# flight_controller.net
KiCad netlist of a schematic drawn in EasyEDA Pro
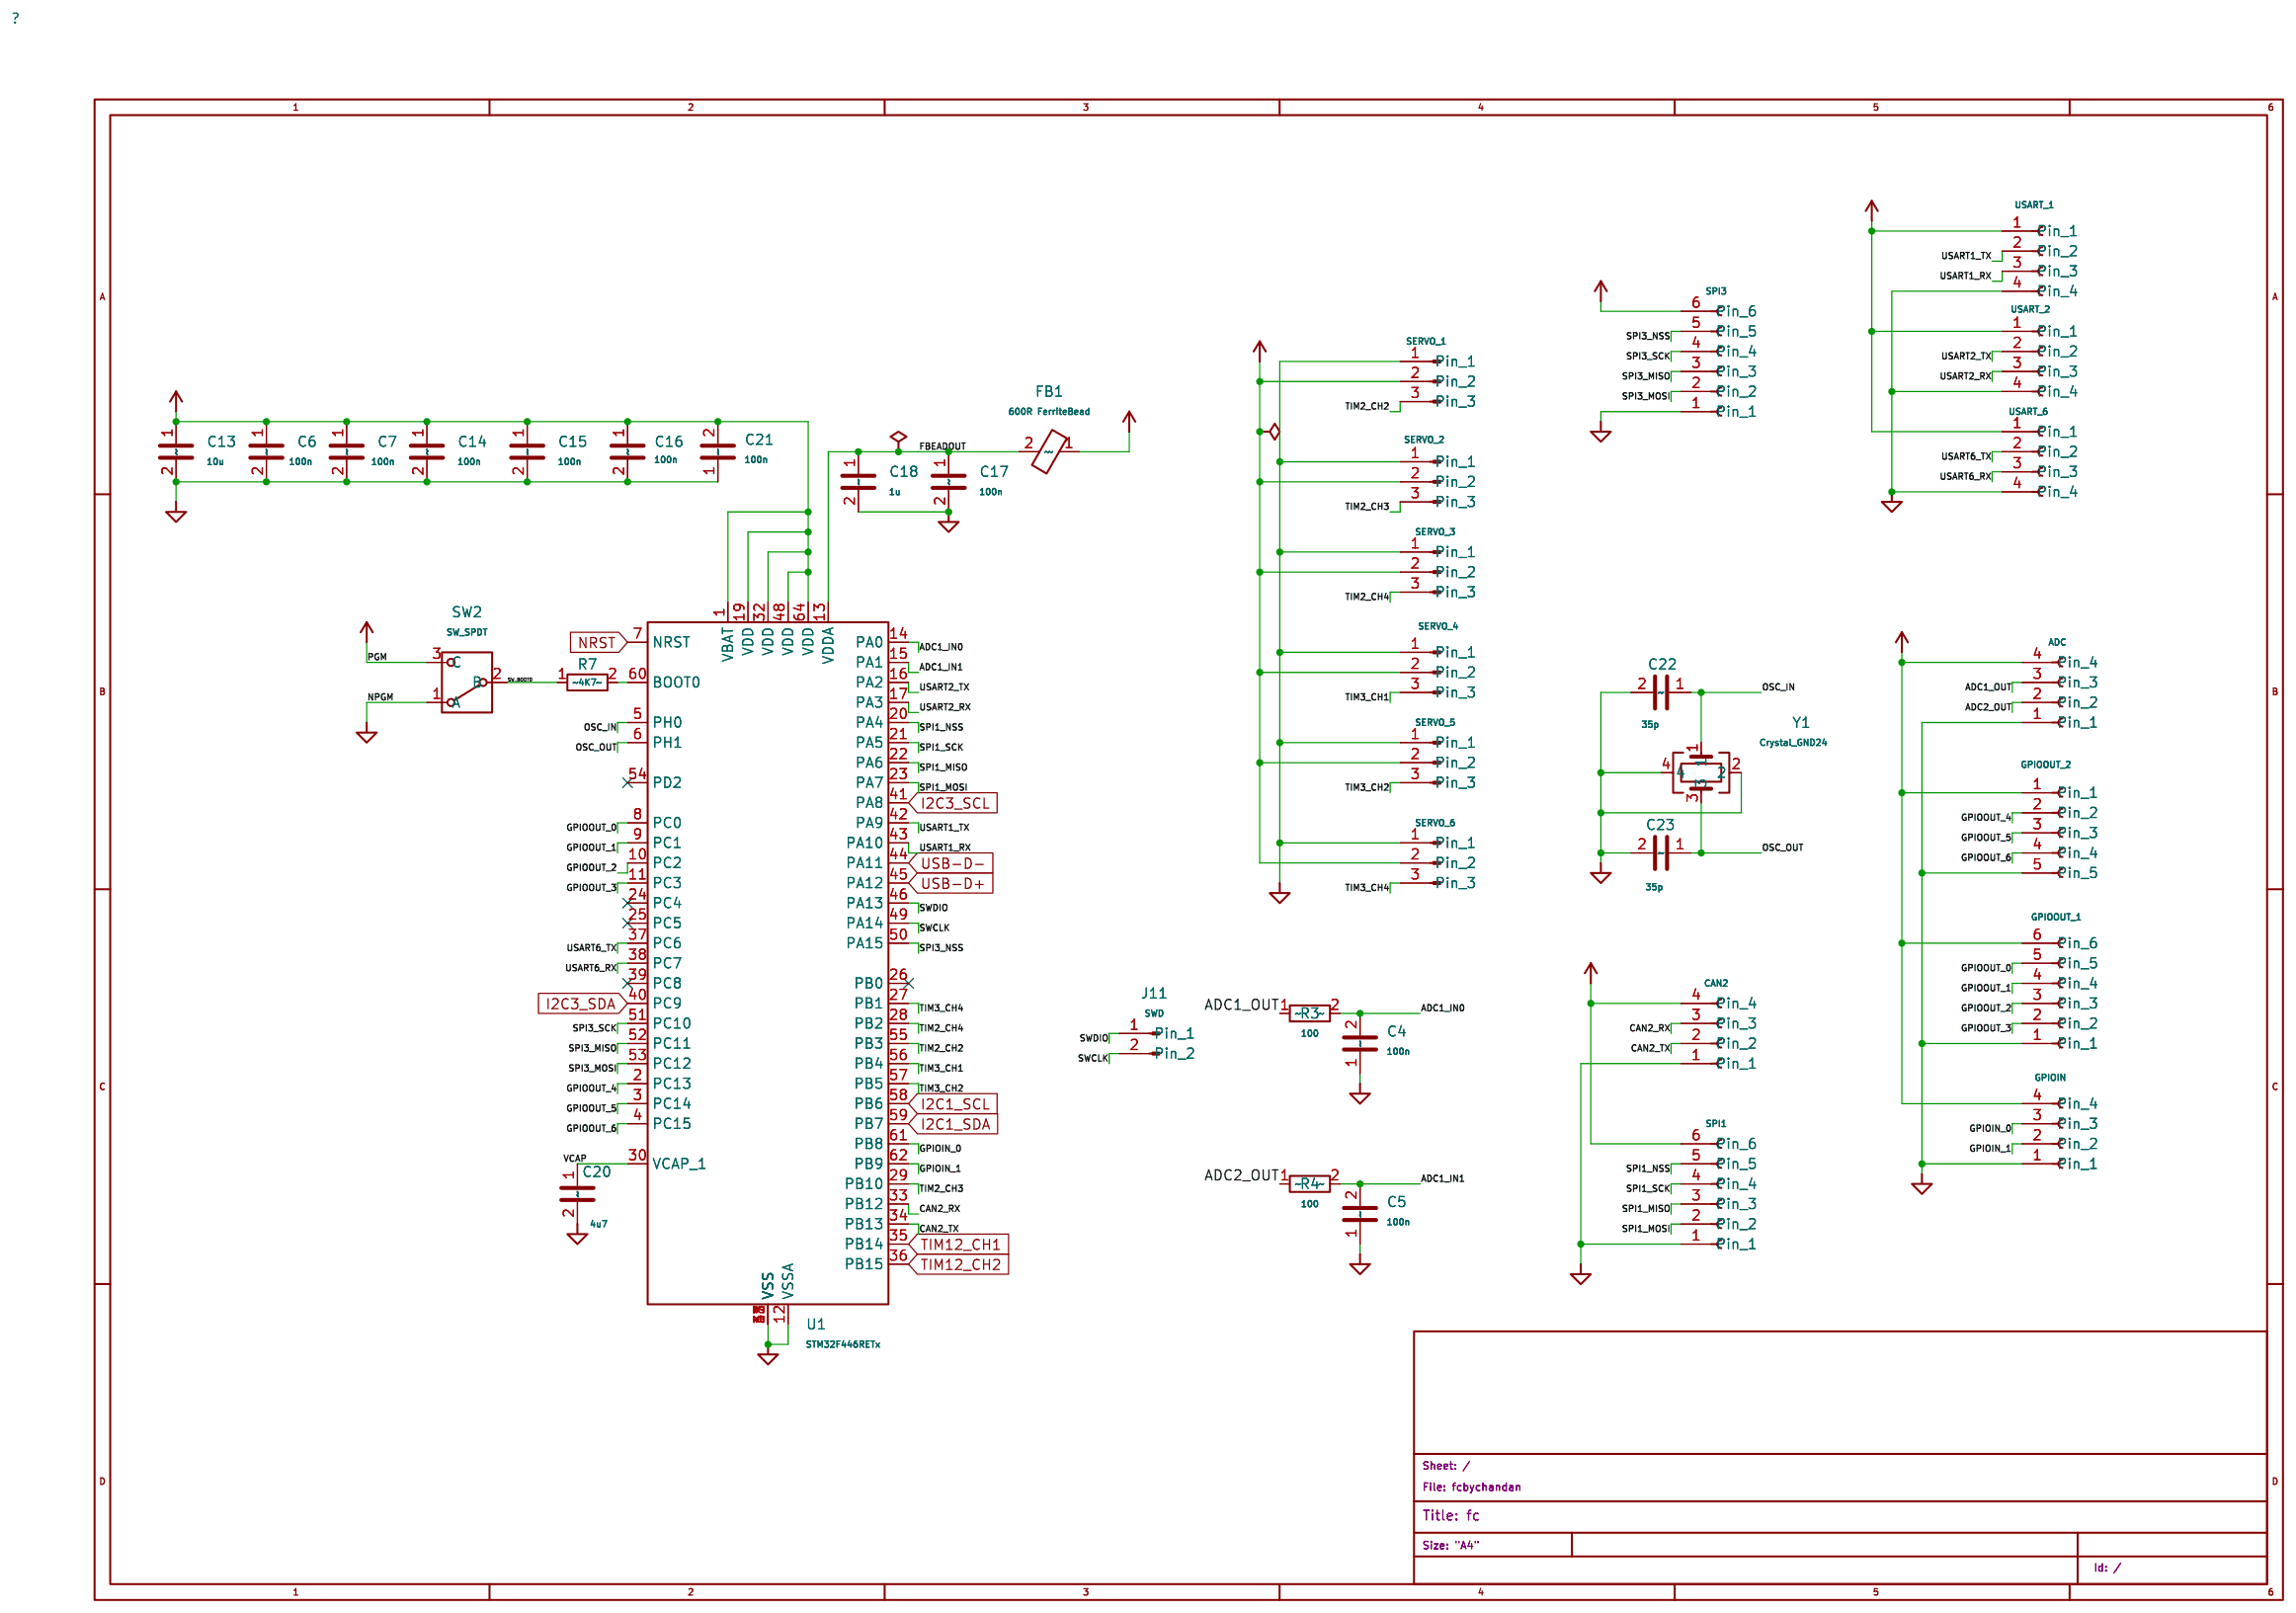
[diagram p0: schematic sheet]

(export (version "E")
  (design (tool "Eeschema 10.0.6"))
  (components
    (comp (ref "C4")
      (value "100n")
      (description "Unpolarized capacitor")
      (libsource (lib "easyedapro") (part "Device_C"))
    )
    (comp (ref "C5")
      (value "100n")
      (description "Unpolarized capacitor")
      (libsource (lib "easyedapro") (part "Device_C"))
    )
    (comp (ref "C6")
      (value "100n")
      (description "Unpolarized capacitor")
      (libsource (lib "easyedapro") (part "Device_C"))
    )
    (comp (ref "C7")
      (value "100n")
      (description "Unpolarized capacitor")
      (libsource (lib "easyedapro") (part "Device_C"))
    )
    (comp (ref "C13")
      (value "10u")
      (description "Unpolarized capacitor")
      (libsource (lib "easyedapro") (part "Device_C"))
    )
    (comp (ref "C14")
      (value "100n")
      (description "Unpolarized capacitor")
      (libsource (lib "easyedapro") (part "Device_C"))
    )
    (comp (ref "C15")
      (value "100n")
      (description "Unpolarized capacitor")
      (libsource (lib "easyedapro") (part "Device_C"))
    )
    (comp (ref "C16")
      (value "100n")
      (description "Unpolarized capacitor")
      (libsource (lib "easyedapro") (part "Device_C"))
    )
    (comp (ref "C17")
      (value "100n")
      (description "Unpolarized capacitor")
      (libsource (lib "easyedapro") (part "Device_C"))
    )
    (comp (ref "C18")
      (value "1u")
      (description "Unpolarized capacitor")
      (libsource (lib "easyedapro") (part "Device_C"))
    )
    (comp (ref "C20")
      (value "4u7")
      (description "Unpolarized capacitor")
      (libsource (lib "easyedapro") (part "Device_C"))
    )
    (comp (ref "C21")
      (value "100n")
      (description "Unpolarized capacitor")
      (libsource (lib "easyedapro") (part "Device_C"))
    )
    (comp (ref "C22")
      (value "35p")
      (description "Unpolarized capacitor")
      (libsource (lib "easyedapro") (part "Device_C"))
    )
    (comp (ref "C23")
      (value "35p")
      (description "Unpolarized capacitor")
      (libsource (lib "easyedapro") (part "Device_C"))
    )
    (comp (ref "FB1")
      (value "600R FerriteBead")
      (description "Ferrite bead")
      (libsource (lib "easyedapro") (part "Device_FerriteBead"))
    )
    (comp (ref "J1")
      (value "SPI3")
      (description "Generic connector, single row, 01x06, script generated")
      (libsource (lib "easyedapro") (part "Connector_Conn_01x06_Socket"))
    )
    (comp (ref "J2")
      (value "GPIOOUT_1")
      (description "Generic connector, single row, 01x06, script generated")
      (libsource (lib "easyedapro") (part "Connector_Conn_01x06_Socket"))
    )
    (comp (ref "J3")
      (value "USART_1")
      (description "Generic connector, single row, 01x04, script generated")
      (libsource (lib "easyedapro") (part "Connector_Conn_01x04_Socket"))
    )
    (comp (ref "J4")
      (value "GPIOIN")
      (description "Generic connector, single row, 01x04, script generated")
      (libsource (lib "easyedapro") (part "Connector_Conn_01x04_Socket"))
    )
    (comp (ref "J5")
      (value "ADC")
      (description "Generic connector, single row, 01x04, script generated")
      (libsource (lib "easyedapro") (part "Connector_Conn_01x04_Socket"))
    )
    (comp (ref "J6")
      (value "USART_2")
      (description "Generic connector, single row, 01x04, script generated")
      (libsource (lib "easyedapro") (part "Connector_Conn_01x04_Socket"))
    )
    (comp (ref "J7")
      (value "USART_6")
      (description "Generic connector, single row, 01x04, script generated")
      (libsource (lib "easyedapro") (part "Connector_Conn_01x04_Socket"))
    )
    (comp (ref "J8")
      (value "SERVO_1")
      (description "Generic connector, single row, 01x03, script generated")
      (libsource (lib "easyedapro") (part "Connector_Conn_01x03_Pin"))
    )
    (comp (ref "J9")
      (value "SERVO_2")
      (description "Generic connector, single row, 01x03, script generated")
      (libsource (lib "easyedapro") (part "Connector_Conn_01x03_Pin"))
    )
    (comp (ref "J10")
      (value "GPIOOUT_2")
      (description "Generic connector, single row, 01x05, script generated")
      (libsource (lib "easyedapro") (part "Connector_Conn_01x05_Socket"))
    )
    (comp (ref "J11")
      (value "SWD")
      (description "Generic connector, single row, 01x02, script generated")
      (libsource (lib "easyedapro") (part "Connector_Conn_01x02_Pin"))
    )
    (comp (ref "J12")
      (value "SERVO_5")
      (description "Generic connector, single row, 01x03, script generated")
      (libsource (lib "easyedapro") (part "Connector_Conn_01x03_Pin"))
    )
    (comp (ref "J13")
      (value "SERVO_4")
      (description "Generic connector, single row, 01x03, script generated")
      (libsource (lib "easyedapro") (part "Connector_Conn_01x03_Pin"))
    )
    (comp (ref "J14")
      (value "SERVO_6")
      (description "Generic connector, single row, 01x03, script generated")
      (libsource (lib "easyedapro") (part "Connector_Conn_01x03_Pin"))
    )
    (comp (ref "J15")
      (value "SERVO_3")
      (description "Generic connector, single row, 01x03, script generated")
      (libsource (lib "easyedapro") (part "Connector_Conn_01x03_Pin"))
    )
    (comp (ref "J17")
      (value "SPI1")
      (description "Generic connector, single row, 01x06, script generated")
      (libsource (lib "easyedapro") (part "Connector_Conn_01x06_Socket"))
    )
    (comp (ref "J18")
      (value "CAN2")
      (description "Generic connector, single row, 01x04, script generated")
      (libsource (lib "easyedapro") (part "Connector_Conn_01x04_Socket"))
    )
    (comp (ref "R3") (value "100") (description "Resistor") (libsource (lib "easyedapro") (part "Device_R")))
    (comp (ref "R4") (value "100") (description "Resistor") (libsource (lib "easyedapro") (part "Device_R")))
    (comp (ref "R7") (value "4K7") (description "Resistor") (libsource (lib "easyedapro") (part "Device_R")))
    (comp (ref "SW2")
      (value "SW_SPDT")
      (description "Switch, single pole double throw")
      (libsource (lib "easyedapro") (part "Switch_SW_SPDT"))
    )
    (comp (ref "U1")
      (value "STM32F446RETx")
      (description "STMicroelectronics Arm Cortex-M4 MCU, 512KB flash, 128KB RAM, 180 MHz, 1.8-3.6V, 50 GPIO, LQFP64")
      (libsource (lib "easyedapro") (part "MCU_ST_STM32F4_STM32F446RETx"))
    )
    (comp (ref "Y1")
      (value "Crystal_GND24")
      (description "Four pin crystal, GND on pins 2 and 4")
      (libsource (lib "easyedapro") (part "Device_Crystal_GND24"))
    )
  )
  (nets
    (net (code "1") (name "/ADC1_IN0") (class "Default")
      (node (ref "C4") (pin "2") (pinfunction "~_2") (pintype "unspecified"))
      (node (ref "R3") (pin "2") (pinfunction "~_2") (pintype "unspecified"))
      (node (ref "U1") (pin "14") (pinfunction "PA0_14") (pintype "bidirectional"))
    )
    (net (code "2") (name "/ADC1_IN1") (class "Default")
      (node (ref "C5") (pin "2") (pinfunction "~_2") (pintype "unspecified"))
      (node (ref "R4") (pin "2") (pinfunction "~_2") (pintype "unspecified"))
      (node (ref "U1") (pin "15") (pinfunction "PA1_15") (pintype "bidirectional"))
    )
    (net (code "3") (name "/ADC1_OUT") (class "Default")
      (node (ref "J5") (pin "3") (pinfunction "Pin_3_3") (pintype "unspecified"))
      (node (ref "R3") (pin "1") (pinfunction "~_1") (pintype "unspecified"))
    )
    (net (code "4") (name "/ADC2_OUT") (class "Default")
      (node (ref "J5") (pin "2") (pinfunction "Pin_2_2") (pintype "unspecified"))
      (node (ref "R4") (pin "1") (pinfunction "~_1") (pintype "unspecified"))
    )
    (net (code "5") (name "/CAN2_RX") (class "Default")
      (node (ref "J18") (pin "3") (pinfunction "Pin_3_3") (pintype "unspecified"))
      (node (ref "U1") (pin "33") (pinfunction "PB12_33") (pintype "bidirectional"))
    )
    (net (code "6") (name "/CAN2_TX") (class "Default")
      (node (ref "J18") (pin "2") (pinfunction "Pin_2_2") (pintype "unspecified"))
      (node (ref "U1") (pin "34") (pinfunction "PB13_34") (pintype "bidirectional"))
    )
    (net (code "7") (name "/GPIOIN_0") (class "Default")
      (node (ref "J4") (pin "3") (pinfunction "Pin_3_3") (pintype "unspecified"))
      (node (ref "U1") (pin "61") (pinfunction "PB8_61") (pintype "bidirectional"))
    )
    (net (code "8") (name "/GPIOIN_1") (class "Default")
      (node (ref "J4") (pin "2") (pinfunction "Pin_2_2") (pintype "unspecified"))
      (node (ref "U1") (pin "62") (pinfunction "PB9_62") (pintype "bidirectional"))
    )
    (net (code "9") (name "/GPIOOUT_0") (class "Default")
      (node (ref "J2") (pin "5") (pinfunction "Pin_5_5") (pintype "unspecified"))
      (node (ref "U1") (pin "8") (pinfunction "PC0_8") (pintype "bidirectional"))
    )
    (net (code "10") (name "/GPIOOUT_1") (class "Default")
      (node (ref "J2") (pin "4") (pinfunction "Pin_4_4") (pintype "unspecified"))
      (node (ref "U1") (pin "9") (pinfunction "PC1_9") (pintype "bidirectional"))
    )
    (net (code "11") (name "/GPIOOUT_2") (class "Default")
      (node (ref "J2") (pin "3") (pinfunction "Pin_3_3") (pintype "unspecified"))
      (node (ref "U1") (pin "10") (pinfunction "PC2_10") (pintype "bidirectional"))
    )
    (net (code "12") (name "/GPIOOUT_3") (class "Default")
      (node (ref "J2") (pin "2") (pinfunction "Pin_2_2") (pintype "unspecified"))
      (node (ref "U1") (pin "11") (pinfunction "PC3_11") (pintype "bidirectional"))
    )
    (net (code "13") (name "/GPIOOUT_4") (class "Default")
      (node (ref "J10") (pin "2") (pinfunction "Pin_2_2") (pintype "unspecified"))
      (node (ref "U1") (pin "2") (pinfunction "PC13_2") (pintype "bidirectional"))
    )
    (net (code "14") (name "/GPIOOUT_5") (class "Default")
      (node (ref "J10") (pin "3") (pinfunction "Pin_3_3") (pintype "unspecified"))
      (node (ref "U1") (pin "3") (pinfunction "PC14_3") (pintype "bidirectional"))
    )
    (net (code "15") (name "/GPIOOUT_6") (class "Default")
      (node (ref "J10") (pin "4") (pinfunction "Pin_4_4") (pintype "unspecified"))
      (node (ref "U1") (pin "4") (pinfunction "PC15_4") (pintype "bidirectional"))
    )
    (net (code "16") (name "/OSC_IN") (class "Default")
      (node (ref "C22") (pin "1") (pinfunction "~_1") (pintype "unspecified"))
      (node (ref "U1") (pin "5") (pinfunction "PH0_5") (pintype "bidirectional"))
      (node (ref "Y1") (pin "1") (pinfunction "1_1") (pintype "unspecified"))
    )
    (net (code "17") (name "/OSC_OUT") (class "Default")
      (node (ref "C23") (pin "1") (pinfunction "~_1") (pintype "unspecified"))
      (node (ref "U1") (pin "6") (pinfunction "PH1_6") (pintype "bidirectional"))
      (node (ref "Y1") (pin "3") (pinfunction "3_3") (pintype "unspecified"))
    )
    (net (code "18") (name "/SPI1_MISO") (class "Default")
      (node (ref "J17") (pin "3") (pinfunction "Pin_3_3") (pintype "unspecified"))
      (node (ref "U1") (pin "22") (pinfunction "PA6_22") (pintype "bidirectional"))
    )
    (net (code "19") (name "/SPI1_MOSI") (class "Default")
      (node (ref "J17") (pin "2") (pinfunction "Pin_2_2") (pintype "unspecified"))
      (node (ref "U1") (pin "23") (pinfunction "PA7_23") (pintype "bidirectional"))
    )
    (net (code "20") (name "/SPI1_NSS") (class "Default")
      (node (ref "J17") (pin "5") (pinfunction "Pin_5_5") (pintype "unspecified"))
      (node (ref "U1") (pin "20") (pinfunction "PA4_20") (pintype "bidirectional"))
    )
    (net (code "21") (name "/SPI1_SCK") (class "Default")
      (node (ref "J17") (pin "4") (pinfunction "Pin_4_4") (pintype "unspecified"))
      (node (ref "U1") (pin "21") (pinfunction "PA5_21") (pintype "bidirectional"))
    )
    (net (code "22") (name "/SPI3_MISO") (class "Default")
      (node (ref "J1") (pin "3") (pinfunction "Pin_3_3") (pintype "unspecified"))
      (node (ref "U1") (pin "52") (pinfunction "PC11_52") (pintype "bidirectional"))
    )
    (net (code "23") (name "/SPI3_MOSI") (class "Default")
      (node (ref "J1") (pin "2") (pinfunction "Pin_2_2") (pintype "unspecified"))
      (node (ref "U1") (pin "53") (pinfunction "PC12_53") (pintype "bidirectional"))
    )
    (net (code "24") (name "/SPI3_NSS") (class "Default")
      (node (ref "J1") (pin "5") (pinfunction "Pin_5_5") (pintype "unspecified"))
      (node (ref "U1") (pin "50") (pinfunction "PA15_50") (pintype "bidirectional"))
    )
    (net (code "25") (name "/SPI3_SCK") (class "Default")
      (node (ref "J1") (pin "4") (pinfunction "Pin_4_4") (pintype "unspecified"))
      (node (ref "U1") (pin "51") (pinfunction "PC10_51") (pintype "bidirectional"))
    )
    (net (code "26") (name "/SWCLK") (class "Default")
      (node (ref "J11") (pin "2") (pinfunction "Pin_2_2") (pintype "unspecified"))
      (node (ref "U1") (pin "49") (pinfunction "PA14_49") (pintype "bidirectional"))
    )
    (net (code "27") (name "/SWDIO") (class "Default")
      (node (ref "J11") (pin "1") (pinfunction "Pin_1_1") (pintype "unspecified"))
      (node (ref "U1") (pin "46") (pinfunction "PA13_46") (pintype "bidirectional"))
    )
    (net (code "28") (name "/SW_BOOT0") (class "Default")
      (node (ref "R7") (pin "1") (pinfunction "~_1") (pintype "unspecified"))
      (node (ref "SW2") (pin "2") (pinfunction "B_2") (pintype "unspecified"))
    )
    (net (code "29") (name "/TIM2_CH2") (class "Default")
      (node (ref "J8") (pin "3") (pinfunction "Pin_3_3") (pintype "unspecified"))
      (node (ref "U1") (pin "55") (pinfunction "PB3_55") (pintype "bidirectional"))
    )
    (net (code "30") (name "/TIM2_CH3") (class "Default")
      (node (ref "J9") (pin "3") (pinfunction "Pin_3_3") (pintype "unspecified"))
      (node (ref "U1") (pin "29") (pinfunction "PB10_29") (pintype "bidirectional"))
    )
    (net (code "31") (name "/TIM2_CH4") (class "Default")
      (node (ref "J15") (pin "3") (pinfunction "Pin_3_3") (pintype "unspecified"))
      (node (ref "U1") (pin "28") (pinfunction "PB2_28") (pintype "bidirectional"))
    )
    (net (code "32") (name "/TIM3_CH1") (class "Default")
      (node (ref "J13") (pin "3") (pinfunction "Pin_3_3") (pintype "unspecified"))
      (node (ref "U1") (pin "56") (pinfunction "PB4_56") (pintype "bidirectional"))
    )
    (net (code "33") (name "/TIM3_CH2") (class "Default")
      (node (ref "J12") (pin "3") (pinfunction "Pin_3_3") (pintype "unspecified"))
      (node (ref "U1") (pin "57") (pinfunction "PB5_57") (pintype "bidirectional"))
    )
    (net (code "34") (name "/TIM3_CH4") (class "Default")
      (node (ref "J14") (pin "3") (pinfunction "Pin_3_3") (pintype "unspecified"))
      (node (ref "U1") (pin "27") (pinfunction "PB1_27") (pintype "bidirectional"))
    )
    (net (code "35") (name "/USART1_RX") (class "Default")
      (node (ref "J3") (pin "3") (pinfunction "Pin_3_3") (pintype "unspecified"))
      (node (ref "U1") (pin "43") (pinfunction "PA10_43") (pintype "bidirectional"))
    )
    (net (code "36") (name "/USART1_TX") (class "Default")
      (node (ref "J3") (pin "2") (pinfunction "Pin_2_2") (pintype "unspecified"))
      (node (ref "U1") (pin "42") (pinfunction "PA9_42") (pintype "bidirectional"))
    )
    (net (code "37") (name "/USART2_RX") (class "Default")
      (node (ref "J6") (pin "3") (pinfunction "Pin_3_3") (pintype "unspecified"))
      (node (ref "U1") (pin "17") (pinfunction "PA3_17") (pintype "bidirectional"))
    )
    (net (code "38") (name "/USART2_TX") (class "Default")
      (node (ref "J6") (pin "2") (pinfunction "Pin_2_2") (pintype "unspecified"))
      (node (ref "U1") (pin "16") (pinfunction "PA2_16") (pintype "bidirectional"))
    )
    (net (code "39") (name "/USART6_RX") (class "Default")
      (node (ref "J7") (pin "3") (pinfunction "Pin_3_3") (pintype "unspecified"))
      (node (ref "U1") (pin "38") (pinfunction "PC7_38") (pintype "bidirectional"))
    )
    (net (code "40") (name "/USART6_TX") (class "Default")
      (node (ref "J7") (pin "2") (pinfunction "Pin_2_2") (pintype "unspecified"))
      (node (ref "U1") (pin "37") (pinfunction "PC6_37") (pintype "bidirectional"))
    )
    (net (code "41") (name "/VCAP") (class "Default")
      (node (ref "C20") (pin "1") (pinfunction "~_1") (pintype "unspecified"))
      (node (ref "U1") (pin "30") (pinfunction "VCAP_1_30") (pintype "unspecified"))
    )
    (net (code "42") (name "I2C1_SCL") (class "Default")
      (node (ref "U1") (pin "58") (pinfunction "PB6_58") (pintype "bidirectional"))
    )
    (net (code "43") (name "I2C1_SDA") (class "Default")
      (node (ref "U1") (pin "59") (pinfunction "PB7_59") (pintype "bidirectional"))
    )
    (net (code "44") (name "I2C3_SCL") (class "Default")
      (node (ref "U1") (pin "41") (pinfunction "PA8_41") (pintype "bidirectional"))
    )
    (net (code "45") (name "I2C3_SDA") (class "Default")
      (node (ref "U1") (pin "40") (pinfunction "PC9_40") (pintype "bidirectional"))
    )
    (net (code "46") (name "NRST") (class "Default")
      (node (ref "U1") (pin "7") (pinfunction "NRST_7") (pintype "input"))
    )
    (net (code "47") (name "Net-(U1-BOOT0)") (class "Default")
      (node (ref "R7") (pin "2") (pinfunction "~_2") (pintype "unspecified"))
      (node (ref "U1") (pin "60") (pinfunction "BOOT0_60") (pintype "input"))
    )
    (net (code "48") (name "POWER_+3.3V") (class "Default")
      (node (ref "J1") (pin "6") (pinfunction "Pin_6_6") (pintype "unspecified"))
      (node (ref "J10") (pin "1") (pinfunction "Pin_1_1") (pintype "unspecified"))
      (node (ref "J17") (pin "6") (pinfunction "Pin_6_6") (pintype "unspecified"))
      (node (ref "J18") (pin "4") (pinfunction "Pin_4_4") (pintype "unspecified"))
      (node (ref "J2") (pin "6") (pinfunction "Pin_6_6") (pintype "unspecified"))
      (node (ref "J3") (pin "1") (pinfunction "Pin_1_1") (pintype "unspecified"))
      (node (ref "J4") (pin "4") (pinfunction "Pin_4_4") (pintype "unspecified"))
      (node (ref "J5") (pin "4") (pinfunction "Pin_4_4") (pintype "unspecified"))
      (node (ref "J6") (pin "1") (pinfunction "Pin_1_1") (pintype "unspecified"))
      (node (ref "J7") (pin "1") (pinfunction "Pin_1_1") (pintype "unspecified"))
    )
    (net (code "49") (name "POWER_+3V3") (class "Default")
      (node (ref "C13") (pin "1") (pinfunction "~_1") (pintype "unspecified"))
      (node (ref "C14") (pin "1") (pinfunction "~_1") (pintype "unspecified"))
      (node (ref "C15") (pin "1") (pinfunction "~_1") (pintype "unspecified"))
      (node (ref "C16") (pin "1") (pinfunction "~_1") (pintype "unspecified"))
      (node (ref "C21") (pin "2") (pinfunction "~_2") (pintype "unspecified"))
      (node (ref "C6") (pin "1") (pinfunction "~_1") (pintype "unspecified"))
      (node (ref "C7") (pin "1") (pinfunction "~_1") (pintype "unspecified"))
      (node (ref "FB1") (pin "1") (pinfunction "~_1") (pintype "unspecified"))
      (node (ref "SW2") (pin "3") (pinfunction "C_3") (pintype "unspecified"))
      (node (ref "U1") (pin "1") (pinfunction "VBAT_1") (pintype "unspecified"))
      (node (ref "U1") (pin "19") (pinfunction "VDD_19") (pintype "unspecified"))
      (node (ref "U1") (pin "32") (pinfunction "VDD_32") (pintype "unspecified"))
      (node (ref "U1") (pin "48") (pinfunction "VDD_48") (pintype "unspecified"))
      (node (ref "U1") (pin "64") (pinfunction "VDD_64") (pintype "unspecified"))
    )
    (net (code "50") (name "POWER_+5V") (class "Default")
      (node (ref "C17") (pin "1") (pinfunction "~_1") (pintype "unspecified"))
      (node (ref "C18") (pin "1") (pinfunction "~_1") (pintype "unspecified"))
      (node (ref "FB1") (pin "2") (pinfunction "~_2") (pintype "unspecified"))
      (node (ref "J12") (pin "2") (pinfunction "Pin_2_2") (pintype "unspecified"))
      (node (ref "J13") (pin "2") (pinfunction "Pin_2_2") (pintype "unspecified"))
      (node (ref "J14") (pin "2") (pinfunction "Pin_2_2") (pintype "unspecified"))
      (node (ref "J15") (pin "2") (pinfunction "Pin_2_2") (pintype "unspecified"))
      (node (ref "J8") (pin "2") (pinfunction "Pin_2_2") (pintype "unspecified"))
      (node (ref "J9") (pin "2") (pinfunction "Pin_2_2") (pintype "unspecified"))
      (node (ref "U1") (pin "13") (pinfunction "VDDA_13") (pintype "unspecified"))
    )
    (net (code "51") (name "POWER_GND") (class "Default")
      (node (ref "C13") (pin "2") (pinfunction "~_2") (pintype "unspecified"))
      (node (ref "C14") (pin "2") (pinfunction "~_2") (pintype "unspecified"))
      (node (ref "C15") (pin "2") (pinfunction "~_2") (pintype "unspecified"))
      (node (ref "C16") (pin "2") (pinfunction "~_2") (pintype "unspecified"))
      (node (ref "C17") (pin "2") (pinfunction "~_2") (pintype "unspecified"))
      (node (ref "C18") (pin "2") (pinfunction "~_2") (pintype "unspecified"))
      (node (ref "C20") (pin "2") (pinfunction "~_2") (pintype "unspecified"))
      (node (ref "C21") (pin "1") (pinfunction "~_1") (pintype "unspecified"))
      (node (ref "C22") (pin "2") (pinfunction "~_2") (pintype "unspecified"))
      (node (ref "C23") (pin "2") (pinfunction "~_2") (pintype "unspecified"))
      (node (ref "C4") (pin "1") (pinfunction "~_1") (pintype "unspecified"))
      (node (ref "C5") (pin "1") (pinfunction "~_1") (pintype "unspecified"))
      (node (ref "C6") (pin "2") (pinfunction "~_2") (pintype "unspecified"))
      (node (ref "C7") (pin "2") (pinfunction "~_2") (pintype "unspecified"))
      (node (ref "J1") (pin "1") (pinfunction "Pin_1_1") (pintype "unspecified"))
      (node (ref "J10") (pin "5") (pinfunction "Pin_5_5") (pintype "unspecified"))
      (node (ref "J12") (pin "1") (pinfunction "Pin_1_1") (pintype "unspecified"))
      (node (ref "J13") (pin "1") (pinfunction "Pin_1_1") (pintype "unspecified"))
      (node (ref "J14") (pin "1") (pinfunction "Pin_1_1") (pintype "unspecified"))
      (node (ref "J15") (pin "1") (pinfunction "Pin_1_1") (pintype "unspecified"))
      (node (ref "J17") (pin "1") (pinfunction "Pin_1_1") (pintype "unspecified"))
      (node (ref "J18") (pin "1") (pinfunction "Pin_1_1") (pintype "unspecified"))
      (node (ref "J2") (pin "1") (pinfunction "Pin_1_1") (pintype "unspecified"))
      (node (ref "J3") (pin "4") (pinfunction "Pin_4_4") (pintype "unspecified"))
      (node (ref "J4") (pin "1") (pinfunction "Pin_1_1") (pintype "unspecified"))
      (node (ref "J5") (pin "1") (pinfunction "Pin_1_1") (pintype "unspecified"))
      (node (ref "J6") (pin "4") (pinfunction "Pin_4_4") (pintype "unspecified"))
      (node (ref "J7") (pin "4") (pinfunction "Pin_4_4") (pintype "unspecified"))
      (node (ref "J8") (pin "1") (pinfunction "Pin_1_1") (pintype "unspecified"))
      (node (ref "J9") (pin "1") (pinfunction "Pin_1_1") (pintype "unspecified"))
      (node (ref "SW2") (pin "1") (pinfunction "A_1") (pintype "unspecified"))
      (node (ref "U1") (pin "12") (pinfunction "VSSA_12") (pintype "unspecified"))
      (node (ref "U1") (pin "18") (pinfunction "VSS_18") (pintype "unspecified"))
      (node (ref "U1") (pin "31") (pinfunction "VSS_31") (pintype "unspecified"))
      (node (ref "U1") (pin "47") (pinfunction "VSS_47") (pintype "unspecified"))
      (node (ref "U1") (pin "63") (pinfunction "VSS_63") (pintype "unspecified"))
      (node (ref "Y1") (pin "2") (pinfunction "2_2") (pintype "unspecified"))
      (node (ref "Y1") (pin "4") (pinfunction "4_4") (pintype "unspecified"))
    )
    (net (code "52") (name "TIM12_CH1") (class "Default")
      (node (ref "U1") (pin "35") (pinfunction "PB14_35") (pintype "bidirectional"))
    )
    (net (code "53") (name "TIM12_CH2") (class "Default")
      (node (ref "U1") (pin "36") (pinfunction "PB15_36") (pintype "bidirectional"))
    )
    (net (code "54") (name "USB-D+") (class "Default")
      (node (ref "U1") (pin "45") (pinfunction "PA12_45") (pintype "bidirectional"))
    )
    (net (code "55") (name "USB-D-") (class "Default")
      (node (ref "U1") (pin "44") (pinfunction "PA11_44") (pintype "bidirectional"))
    )
    (net (code "56") (name "unconnected-(U1-PB0-Pad26)") (class "Default")
      (node (ref "U1") (pin "26") (pinfunction "PB0_26") (pintype "bidirectional+no_connect"))
    )
    (net (code "57") (name "unconnected-(U1-PC4-Pad24)") (class "Default")
      (node (ref "U1") (pin "24") (pinfunction "PC4_24") (pintype "bidirectional+no_connect"))
    )
    (net (code "58") (name "unconnected-(U1-PC5-Pad25)") (class "Default")
      (node (ref "U1") (pin "25") (pinfunction "PC5_25") (pintype "bidirectional+no_connect"))
    )
    (net (code "59") (name "unconnected-(U1-PC8-Pad39)") (class "Default")
      (node (ref "U1") (pin "39") (pinfunction "PC8_39") (pintype "bidirectional+no_connect"))
    )
    (net (code "60") (name "unconnected-(U1-PD2-Pad54)") (class "Default")
      (node (ref "U1") (pin "54") (pinfunction "PD2_54") (pintype "bidirectional+no_connect"))
    )
  )
)
